# esp8266.net
KiCad netlist of a schematic drawn in Altium Designer
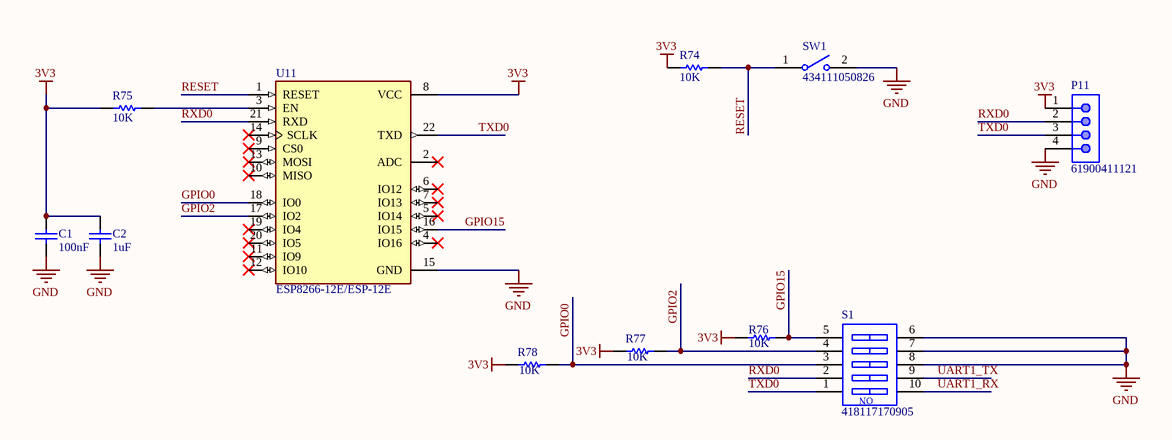
[diagram p0: esp8266.SchDoc]

(export (version "E")
  (design (tool "Eeschema 10.0.6"))
  (components
    (comp (ref "C1")
      (value "100nF")
      (footprint "CAP-SM-0603")
      (description "Capacitor")
      (fields (field (name "Comment") "Cap Non-Pol SMD"))
      (libsource (lib "PIF_Library") (part "Cap Non-Pol SMD"))
    )
    (comp (ref "C2")
      (value "1uF")
      (footprint "CAP-SM-0603")
      (description "Capacitor")
      (fields (field (name "Comment") "Cap Non-Pol SMD"))
      (libsource (lib "PIF_Library") (part "Cap Non-Pol SMD"))
    )
    (comp (ref "P11")
      (value "61900411121")
      (footprint "61900411121")
      (description "WR-WTB THT Male Vertical Locking Header, pitch 2.54mm, 4p")
      (fields (field (name "PUBLISHER") "Wurth Elektronik"))
      (libsource (lib "653008114822_Altium_WR-WTB_rev20a") (part "61900411121"))
    )
    (comp (ref "R74")
      (value "10K")
      (footprint "RES-SM-0603")
      (description "Resistor")
      (fields (field (name "Comment") "RESISTOR SMD"))
      (libsource (lib "PIF_Library") (part "RESISTOR SMD"))
    )
    (comp (ref "R75")
      (value "10K")
      (footprint "RES-SM-0603")
      (description "Resistor")
      (fields (field (name "Comment") "RESISTOR SMD"))
      (libsource (lib "PIF_Library") (part "RESISTOR SMD"))
    )
    (comp (ref "R76")
      (value "10K")
      (footprint "RES-SM-0603")
      (description "Resistor")
      (fields (field (name "Comment") "RESISTOR SMD"))
      (libsource (lib "PIF_Library") (part "RESISTOR SMD"))
    )
    (comp (ref "R77")
      (value "10K")
      (footprint "RES-SM-0603")
      (description "Resistor")
      (fields (field (name "Comment") "RESISTOR SMD"))
      (libsource (lib "PIF_Library") (part "RESISTOR SMD"))
    )
    (comp (ref "R78")
      (value "10K")
      (footprint "RES-SM-0603")
      (description "Resistor")
      (fields (field (name "Comment") "RESISTOR SMD"))
      (libsource (lib "PIF_Library") (part "RESISTOR SMD"))
    )
    (comp (ref "S1")
      (value "418117170905")
      (footprint "418117170905")
      (description "WS-DITV Compact THT Dip Switch, Flat Actuator, pitch 2.54mm, 5p")
      (fields (field (name "PUBLISHER") "Wurth Elektronik"))
      (libsource (lib "Altium_WS-DITV (rev19a)") (part "418117170905"))
    )
    (comp (ref "SW1")
      (value "434111050826")
      (footprint "WS-TASV_L6W3.5H5_4341x10508x6")
      (description "WS-TASV SMT Tact Switch, 12VDC, 50mA, 260g, height 5mm")
      (fields (field (name "MANUFACTURER") "Wurth Elektronik"))
      (libsource (lib "Altium_WS-TASV (rev22a)") (part "434111050826"))
    )
    (comp (ref "U11")
      (value "ESP8266-12E/ESP-12E")
      (footprint "XCVR_ESP8266-12E/ESP-12E")
      (description "ESP-12E WiFi Module")
      (libsource (lib "ESP8266-12E_ESP-12E") (part "ESP8266-12E/ESP-12E"))
    )
  )
  (nets
    (net (code "1") (name "/GPIO0") (class "Default")
      (node (ref "R78") (pin "1") (pinfunction "1_1") (pintype "passive"))
      (node (ref "S1") (pin "3") (pinfunction "3_3") (pintype "passive"))
      (node (ref "U11") (pin "18") (pinfunction "IO0_18") (pintype "bidirectional"))
    )
    (net (code "2") (name "/GPIO2") (class "Default")
      (node (ref "R77") (pin "1") (pinfunction "1_1") (pintype "passive"))
      (node (ref "S1") (pin "4") (pinfunction "4_4") (pintype "passive"))
      (node (ref "U11") (pin "17") (pinfunction "IO2_17") (pintype "bidirectional"))
    )
    (net (code "3") (name "/GPIO15") (class "Default")
      (node (ref "R76") (pin "1") (pinfunction "1_1") (pintype "passive"))
      (node (ref "S1") (pin "5") (pinfunction "5_5") (pintype "passive"))
      (node (ref "U11") (pin "16") (pinfunction "IO15_16") (pintype "bidirectional"))
    )
    (net (code "4") (name "/RESET") (class "Default")
      (node (ref "R74") (pin "2") (pinfunction "2_2") (pintype "passive"))
      (node (ref "SW1") (pin "1") (pinfunction "1_1") (pintype "passive"))
      (node (ref "U11") (pin "1") (pinfunction "RESET_1") (pintype "input"))
    )
    (net (code "5") (name "/RXD0") (class "Default")
      (node (ref "P11") (pin "2") (pinfunction "2_2") (pintype "passive"))
      (node (ref "S1") (pin "2") (pinfunction "2_2") (pintype "passive"))
      (node (ref "U11") (pin "21") (pinfunction "RXD_21") (pintype "input"))
    )
    (net (code "6") (name "/TXD0") (class "Default")
      (node (ref "P11") (pin "3") (pinfunction "3_3") (pintype "passive"))
      (node (ref "S1") (pin "1") (pinfunction "1_1") (pintype "passive"))
      (node (ref "U11") (pin "22") (pinfunction "TXD_22") (pintype "output"))
    )
    (net (code "7") (name "/UART1_RX") (class "Default")
      (node (ref "S1") (pin "10") (pinfunction "10_10") (pintype "passive"))
    )
    (net (code "8") (name "/UART1_TX") (class "Default")
      (node (ref "S1") (pin "9") (pinfunction "9_9") (pintype "passive"))
    )
    (net (code "9") (name "3V3") (class "Default")
      (node (ref "C1") (pin "2") (pinfunction "2_2") (pintype "passive"))
      (node (ref "C2") (pin "2") (pinfunction "2_2") (pintype "passive"))
      (node (ref "P11") (pin "1") (pinfunction "1_1") (pintype "passive"))
      (node (ref "R74") (pin "1") (pinfunction "1_1") (pintype "passive"))
      (node (ref "R75") (pin "1") (pinfunction "1_1") (pintype "passive"))
      (node (ref "R76") (pin "2") (pinfunction "2_2") (pintype "passive"))
      (node (ref "R77") (pin "2") (pinfunction "2_2") (pintype "passive"))
      (node (ref "R78") (pin "2") (pinfunction "2_2") (pintype "passive"))
      (node (ref "U11") (pin "8") (pinfunction "VCC_8") (pintype "power_in"))
    )
    (net (code "10") (name "GND") (class "Default")
      (node (ref "C1") (pin "1") (pinfunction "1_1") (pintype "passive"))
      (node (ref "C2") (pin "1") (pinfunction "1_1") (pintype "passive"))
      (node (ref "P11") (pin "4") (pinfunction "4_4") (pintype "passive"))
      (node (ref "S1") (pin "6") (pinfunction "6_6") (pintype "passive"))
      (node (ref "S1") (pin "7") (pinfunction "7_7") (pintype "passive"))
      (node (ref "S1") (pin "8") (pinfunction "8_8") (pintype "passive"))
      (node (ref "SW1") (pin "2") (pinfunction "2_2") (pintype "passive"))
      (node (ref "U11") (pin "15") (pinfunction "GND_15") (pintype "power_in"))
    )
    (net (code "11") (name "Net-(U11-EN)") (class "Default")
      (node (ref "R75") (pin "2") (pinfunction "2_2") (pintype "passive"))
      (node (ref "U11") (pin "3") (pinfunction "EN_3") (pintype "input"))
    )
    (net (code "12") (name "unconnected-(U11-ADC-Pad2)") (class "Default")
      (node (ref "U11") (pin "2") (pinfunction "ADC_2") (pintype "passive+no_connect"))
    )
    (net (code "13") (name "unconnected-(U11-CS0-Pad9)") (class "Default")
      (node (ref "U11") (pin "9") (pinfunction "CS0_9") (pintype "input+no_connect"))
    )
    (net (code "14") (name "unconnected-(U11-IO4-Pad19)") (class "Default")
      (node (ref "U11") (pin "19") (pinfunction "IO4_19") (pintype "bidirectional+no_connect"))
    )
    (net (code "15") (name "unconnected-(U11-IO5-Pad20)") (class "Default")
      (node (ref "U11") (pin "20") (pinfunction "IO5_20") (pintype "bidirectional+no_connect"))
    )
    (net (code "16") (name "unconnected-(U11-IO9-Pad11)") (class "Default")
      (node (ref "U11") (pin "11") (pinfunction "IO9_11") (pintype "bidirectional+no_connect"))
    )
    (net (code "17") (name "unconnected-(U11-IO10-Pad12)") (class "Default")
      (node (ref "U11") (pin "12") (pinfunction "IO10_12") (pintype "bidirectional+no_connect"))
    )
    (net (code "18") (name "unconnected-(U11-IO12-Pad6)") (class "Default")
      (node (ref "U11") (pin "6") (pinfunction "IO12_6") (pintype "bidirectional+no_connect"))
    )
    (net (code "19") (name "unconnected-(U11-IO13-Pad7)") (class "Default")
      (node (ref "U11") (pin "7") (pinfunction "IO13_7") (pintype "bidirectional+no_connect"))
    )
    (net (code "20") (name "unconnected-(U11-IO14-Pad5)") (class "Default")
      (node (ref "U11") (pin "5") (pinfunction "IO14_5") (pintype "bidirectional+no_connect"))
    )
    (net (code "21") (name "unconnected-(U11-IO16-Pad4)") (class "Default")
      (node (ref "U11") (pin "4") (pinfunction "IO16_4") (pintype "bidirectional+no_connect"))
    )
    (net (code "22") (name "unconnected-(U11-MISO-Pad10)") (class "Default")
      (node (ref "U11") (pin "10") (pinfunction "MISO_10") (pintype "bidirectional+no_connect"))
    )
    (net (code "23") (name "unconnected-(U11-MOSI-Pad13)") (class "Default")
      (node (ref "U11") (pin "13") (pinfunction "MOSI_13") (pintype "bidirectional+no_connect"))
    )
    (net (code "24") (name "unconnected-(U11-SCLK-Pad14)") (class "Default")
      (node (ref "U11") (pin "14") (pinfunction "SCLK_14") (pintype "input+no_connect"))
    )
  )
)
